# Total.net
KiCad netlist of a schematic drawn in Altium Designer
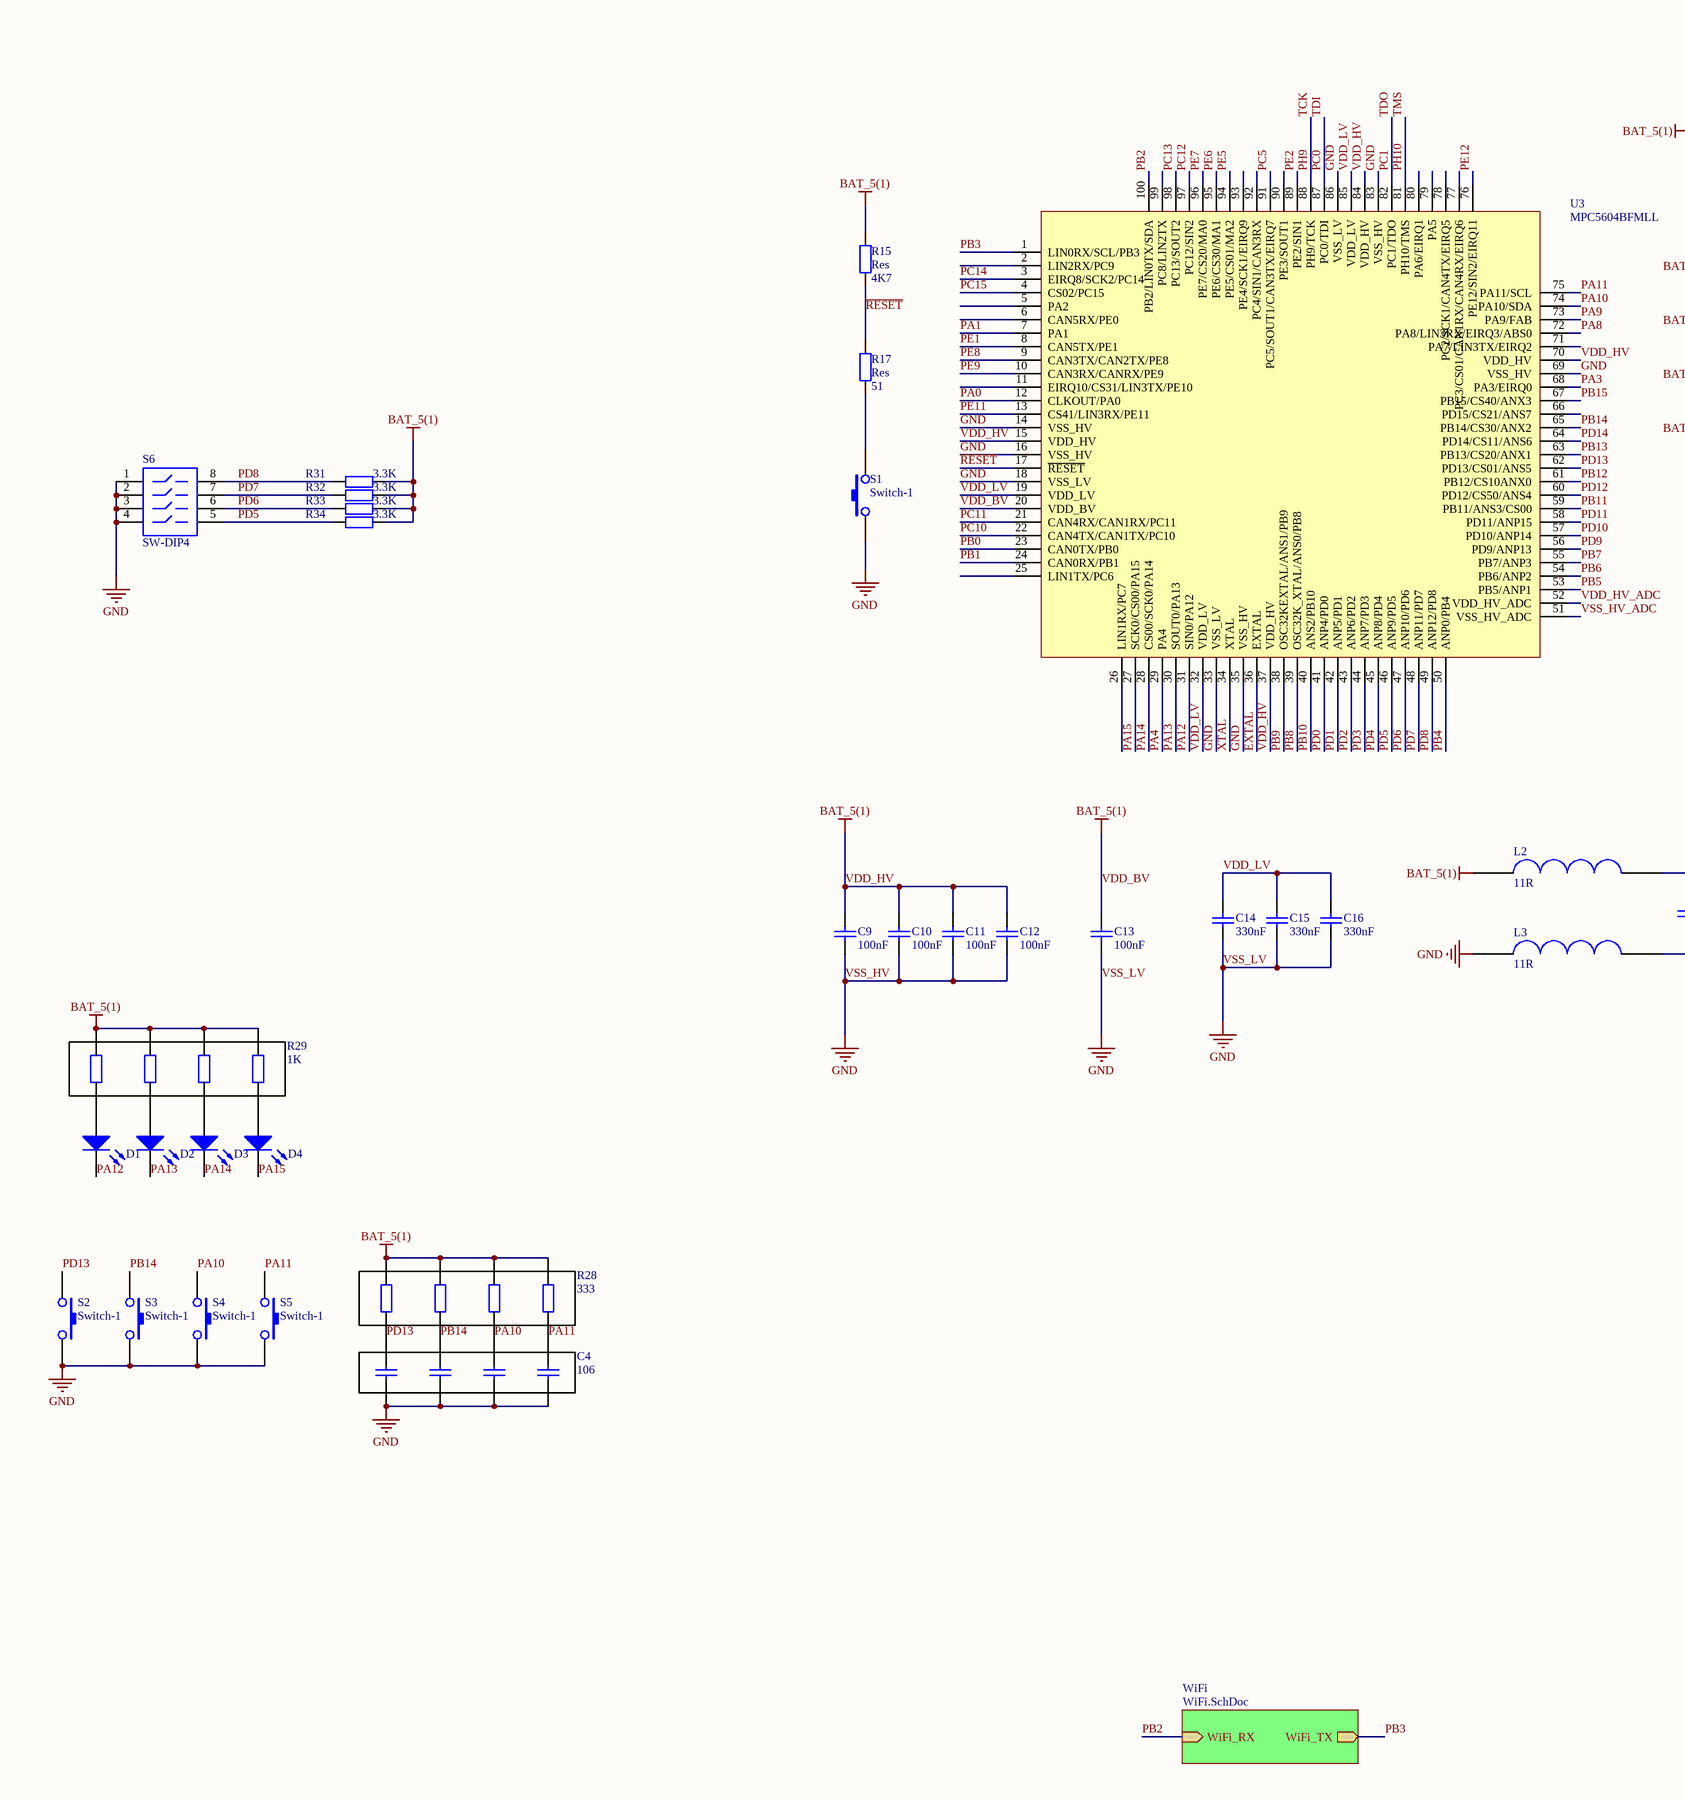
[diagram p0: Total.SchDoc, left]
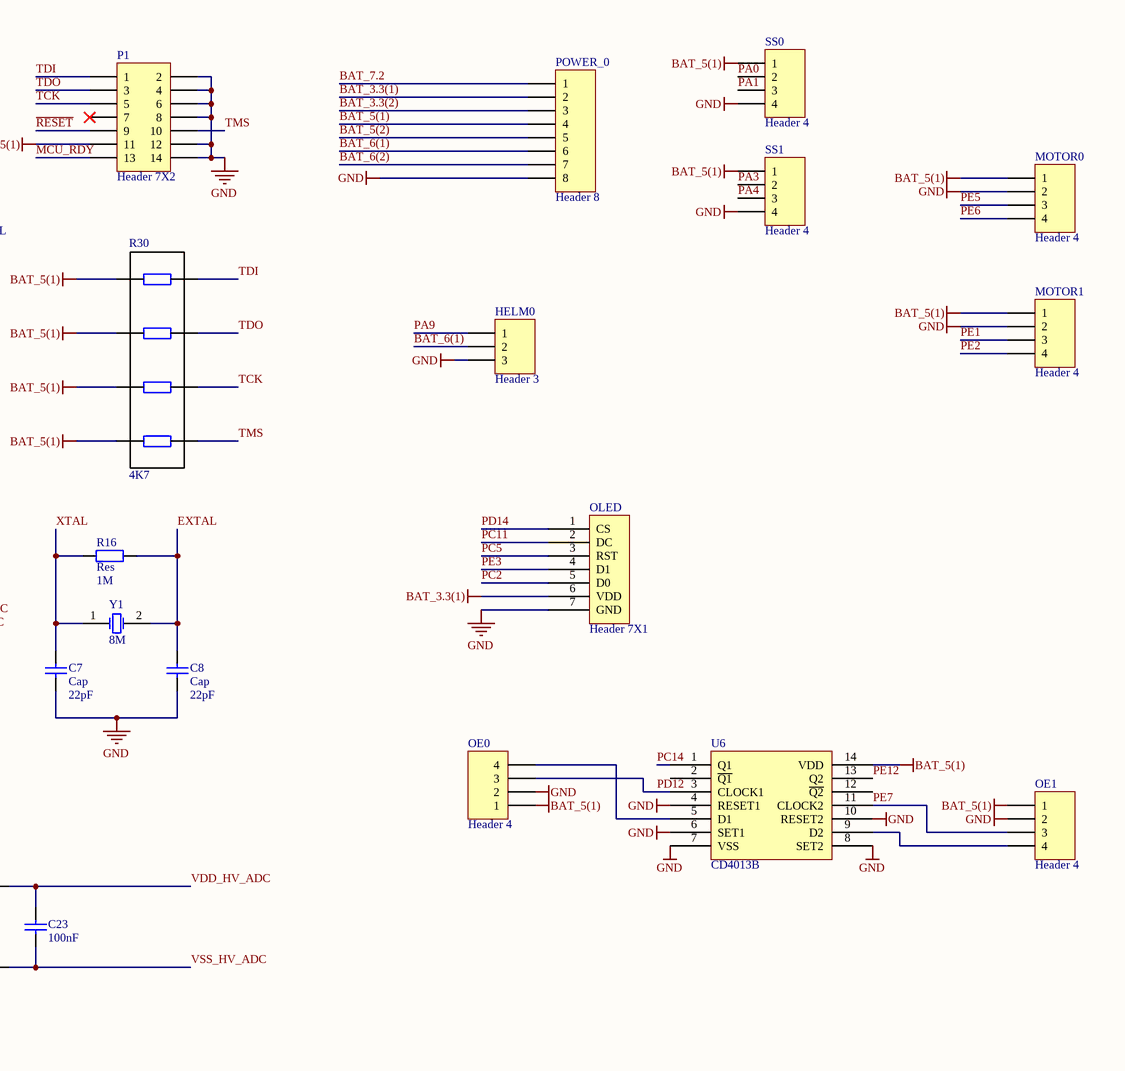
[diagram p1: Total.SchDoc, right]

(export (version "E")
  (design (tool "Eeschema 10.0.6"))
  (components
    (comp (ref "C4")
      (value "106")
      (footprint "8P4R-0603")
      (fields (field (name "Comment") "Cap x4"))
      (libsource (lib "SmartCarCreative") (part "Cap x4"))
    )
    (comp (ref "C7")
      (value "Cap")
      (footprint "0805 2")
      (description "Capacitor")
      (fields (field (name "ALTIUM_VALUE") "22pF") (field (name "PUBLISHER") "Altium Limited"))
      (libsource (lib "SmartCarCreative") (part "Cap"))
    )
    (comp (ref "C8")
      (value "Cap")
      (footprint "0805 2")
      (description "Capacitor")
      (fields (field (name "ALTIUM_VALUE") "22pF") (field (name "PUBLISHER") "Altium Limited"))
      (libsource (lib "SmartCarCreative") (part "Cap"))
    )
    (comp (ref "C9")
      (value "100nF")
      (footprint "0805 2")
      (description "Capacitor")
      (fields (field (name "Comment") "Cap") (field (name "PUBLISHER") "Altium Limited"))
      (libsource (lib "SmartCarCreative") (part "Cap"))
    )
    (comp (ref "C10")
      (value "100nF")
      (footprint "0805 2")
      (description "Capacitor")
      (fields (field (name "Comment") "Cap") (field (name "PUBLISHER") "Altium Limited"))
      (libsource (lib "SmartCarCreative") (part "Cap"))
    )
    (comp (ref "C11")
      (value "100nF")
      (footprint "0805 2")
      (description "Capacitor")
      (fields (field (name "Comment") "Cap") (field (name "PUBLISHER") "Altium Limited"))
      (libsource (lib "SmartCarCreative") (part "Cap"))
    )
    (comp (ref "C12")
      (value "100nF")
      (footprint "0805 2")
      (description "Capacitor")
      (fields (field (name "Comment") "Cap") (field (name "PUBLISHER") "Altium Limited"))
      (libsource (lib "SmartCarCreative") (part "Cap"))
    )
    (comp (ref "C13")
      (value "100nF")
      (footprint "0805 2")
      (description "Capacitor")
      (fields (field (name "Comment") "Cap") (field (name "PUBLISHER") "Altium Limited"))
      (libsource (lib "SmartCarCreative") (part "Cap"))
    )
    (comp (ref "C14")
      (value "330nF")
      (footprint "0805 2")
      (description "Capacitor")
      (fields (field (name "Comment") "Cap") (field (name "PUBLISHER") "Altium Limited"))
      (libsource (lib "SmartCarCreative") (part "Cap"))
    )
    (comp (ref "C15")
      (value "330nF")
      (footprint "0805 2")
      (description "Capacitor")
      (fields (field (name "Comment") "Cap") (field (name "PUBLISHER") "Altium Limited"))
      (libsource (lib "SmartCarCreative") (part "Cap"))
    )
    (comp (ref "C16")
      (value "330nF")
      (footprint "0805 2")
      (description "Capacitor")
      (fields (field (name "Comment") "Cap") (field (name "PUBLISHER") "Altium Limited"))
      (libsource (lib "SmartCarCreative") (part "Cap"))
    )
    (comp (ref "C23")
      (value "100nF")
      (footprint "0805 2")
      (description "Capacitor")
      (fields (field (name "Comment") "Cap") (field (name "PUBLISHER") "Altium Limited"))
      (libsource (lib "SmartCarCreative") (part "Cap"))
    )
    (comp (ref "D1") (value "LED") (footprint "0805 Pol 3") (libsource (lib "SmartCarCreative") (part "LED")))
    (comp (ref "D2") (value "LED") (footprint "0805 Pol 3") (libsource (lib "SmartCarCreative") (part "LED")))
    (comp (ref "D3") (value "LED") (footprint "0805 Pol 3") (libsource (lib "SmartCarCreative") (part "LED")))
    (comp (ref "D4") (value "LED") (footprint "0805 Pol 3") (libsource (lib "SmartCarCreative") (part "LED")))
    (comp (ref "HELM0")
      (value "Header 3")
      (footprint "HDR1X3")
      (description "Header, 3-Pin")
      (fields (field (name "PUBLISHER") "Altium Limited"))
      (libsource (lib "Miscellaneous Connectors") (part "Header 3"))
    )
    (comp (ref "L2")
      (value "11R")
      (footprint "0805 2")
      (fields (field (name "Comment") "Bead"))
      (libsource (lib "SmartCarCreative") (part "Bead"))
    )
    (comp (ref "L3")
      (value "11R")
      (footprint "0805 2")
      (fields (field (name "Comment") "Bead"))
      (libsource (lib "SmartCarCreative") (part "Bead"))
    )
    (comp (ref "MOTOR0")
      (value "Header 4")
      (footprint "HDR1X4")
      (description "Header, 4-Pin")
      (fields (field (name "PUBLISHER") "Altium Limited"))
      (libsource (lib "Miscellaneous Connectors") (part "Header 4"))
    )
    (comp (ref "MOTOR1")
      (value "Header 4")
      (footprint "HDR1X4")
      (description "Header, 4-Pin")
      (fields (field (name "PUBLISHER") "Altium Limited"))
      (libsource (lib "Miscellaneous Connectors") (part "Header 4"))
    )
    (comp (ref "OE0")
      (value "Header 4")
      (footprint "HDR1X4")
      (description "Header, 4-Pin")
      (fields (field (name "PUBLISHER") "Altium Limited"))
      (libsource (lib "") (part "Header 4_1"))
    )
    (comp (ref "OE1")
      (value "Header 4")
      (footprint "HDR1X4")
      (description "Header, 4-Pin")
      (fields (field (name "PUBLISHER") "Altium Limited"))
      (libsource (lib "Miscellaneous Connectors") (part "Header 4"))
    )
    (comp (ref "OLED")
      (value "Header 7X1")
      (footprint "OLED-chiusir")
      (libsource (lib "SmartCarCreative") (part "OLED-chiusir"))
    )
    (comp (ref "P1")
      (value "Header 7X2")
      (footprint "Header 2X7")
      (description "Header, 7-Pin, Dual row")
      (fields (field (name "PUBLISHER") "Altium Limited"))
      (libsource (lib "SmartCarCreative") (part "Header 7X2"))
    )
    (comp (ref "POWER_0")
      (value "Header 8")
      (footprint "XH2.54_8")
      (description "Header, 8-Pin")
      (fields (field (name "PUBLISHER") "Altium Limited"))
      (libsource (lib "SmartCarCreative") (part "Header 8"))
    )
    (comp (ref "R15")
      (value "Res")
      (footprint "0805 2")
      (description "Resistor")
      (fields (field (name "ALTIUM_VALUE") "4K7") (field (name "PUBLISHER") "Altium Limited"))
      (libsource (lib "") (part "Res_1"))
    )
    (comp (ref "R16")
      (value "Res")
      (footprint "0805 2")
      (description "Resistor")
      (fields (field (name "ALTIUM_VALUE") "1M") (field (name "PUBLISHER") "Altium Limited"))
      (libsource (lib "SmartCarCreative") (part "Res"))
    )
    (comp (ref "R17")
      (value "Res")
      (footprint "0805 2")
      (description "Resistor")
      (fields (field (name "ALTIUM_VALUE") "51") (field (name "PUBLISHER") "Altium Limited"))
      (libsource (lib "") (part "Res_1"))
    )
    (comp (ref "R28")
      (value "333")
      (footprint "8P4R-0603")
      (fields (field (name "Comment") "R x4"))
      (libsource (lib "") (part "Res x4_1"))
    )
    (comp (ref "R29")
      (value "1K")
      (footprint "8P4R-0603")
      (fields (field (name "Comment") "R x4"))
      (libsource (lib "") (part "Res x4_1"))
    )
    (comp (ref "R30")
      (value "4K7")
      (footprint "8P4R-0603")
      (fields (field (name "Comment") "R x4"))
      (libsource (lib "SmartCarCreative") (part "Res x4"))
    )
    (comp (ref "R31")
      (value "3.3K")
      (footprint "0805 2")
      (description "Resistor")
      (fields (field (name "Comment") "Res2") (field (name "PUBLISHER") "Altium Limited"))
      (libsource (lib "Miscellaneous Devices") (part "Res2"))
    )
    (comp (ref "R32")
      (value "3.3K")
      (footprint "0805 2")
      (description "Resistor")
      (fields (field (name "Comment") "Res2") (field (name "PUBLISHER") "Altium Limited"))
      (libsource (lib "Miscellaneous Devices") (part "Res2"))
    )
    (comp (ref "R33")
      (value "3.3K")
      (footprint "0805 2")
      (description "Resistor")
      (fields (field (name "Comment") "Res2") (field (name "PUBLISHER") "Altium Limited"))
      (libsource (lib "Miscellaneous Devices") (part "Res2"))
    )
    (comp (ref "R34")
      (value "3.3K")
      (footprint "0805 2")
      (description "Resistor")
      (fields (field (name "Comment") "Res2") (field (name "PUBLISHER") "Altium Limited"))
      (libsource (lib "Miscellaneous Devices") (part "Res2"))
    )
    (comp (ref "S1")
      (value "Switch-1")
      (footprint "轻触按键")
      (libsource (lib "SmartCarCreative") (part "Switch-1"))
    )
    (comp (ref "S2")
      (value "Switch-1")
      (footprint "轻触按键")
      (libsource (lib "SmartCarCreative") (part "Switch-1"))
    )
    (comp (ref "S3")
      (value "Switch-1")
      (footprint "轻触按键")
      (libsource (lib "SmartCarCreative") (part "Switch-1"))
    )
    (comp (ref "S4")
      (value "Switch-1")
      (footprint "轻触按键")
      (libsource (lib "SmartCarCreative") (part "Switch-1"))
    )
    (comp (ref "S5")
      (value "Switch-1")
      (footprint "轻触按键")
      (libsource (lib "SmartCarCreative") (part "Switch-1"))
    )
    (comp (ref "S6")
      (value "SW-DIP4")
      (footprint "Switch_4")
      (libsource (lib "SystemBoard2015") (part "SWITCH-4"))
    )
    (comp (ref "SS0")
      (value "Header 4")
      (footprint "HDR1X4")
      (description "Header, 4-Pin")
      (fields (field (name "PUBLISHER") "Altium Limited"))
      (libsource (lib "Miscellaneous Connectors") (part "Header 4"))
    )
    (comp (ref "SS1")
      (value "Header 4")
      (footprint "HDR1X4")
      (description "Header, 4-Pin")
      (fields (field (name "PUBLISHER") "Altium Limited"))
      (libsource (lib "Miscellaneous Connectors") (part "Header 4"))
    )
    (comp (ref "U3")
      (value "MPC5604BFMLL")
      (footprint "LQ_LQFP100")
      (libsource (lib "SmartCarCreative") (part "MPC5604BFMLL"))
    )
    (comp (ref "U6")
      (value "CD4013B")
      (footprint "TSOP-14")
      (description "CMOS Dual 'D'-Type Flip-Flop")
      (libsource (lib "SmartCarCreative") (part "CD4013B"))
    )
    (comp (ref "Y1")
      (value "8M")
      (footprint "5032 2")
      (description "Crystal Oscillator")
      (fields (field (name "Comment") "XTAL") (field (name "PUBLISHER") "Altium Limited"))
      (libsource (lib "SmartCarCreative") (part "XTAL"))
    )
  )
  (nets
    (net (code "1") (name "/BAT_3.3(2)") (class "Default")
      (node (ref "POWER_0") (pin "3") (pinfunction "3_3") (pintype "passive"))
    )
    (net (code "2") (name "/BAT_5(2)") (class "Default")
      (node (ref "POWER_0") (pin "5") (pinfunction "5_5") (pintype "passive"))
    )
    (net (code "3") (name "/BAT_6(1)") (class "Default")
      (node (ref "HELM0") (pin "2") (pinfunction "2_2") (pintype "passive"))
      (node (ref "POWER_0") (pin "6") (pinfunction "6_6") (pintype "passive"))
    )
    (net (code "4") (name "/BAT_6(2)") (class "Default")
      (node (ref "POWER_0") (pin "7") (pinfunction "7_7") (pintype "passive"))
    )
    (net (code "5") (name "/BAT_7.2") (class "Default")
      (node (ref "POWER_0") (pin "1") (pinfunction "1_1") (pintype "passive"))
    )
    (net (code "6") (name "/EXTAL") (class "Default")
      (node (ref "C8") (pin "2") (pinfunction "2_2") (pintype "passive"))
      (node (ref "R16") (pin "1") (pinfunction "1_1") (pintype "passive"))
      (node (ref "U3") (pin "36") (pinfunction "EXTAL_36") (pintype "passive"))
      (node (ref "Y1") (pin "2") (pinfunction "OSC2_2") (pintype "passive"))
    )
    (net (code "7") (name "/MCU_RDY") (class "Default")
      (node (ref "P1") (pin "13") (pinfunction "13_13") (pintype "passive"))
    )
    (net (code "8") (name "/PA0") (class "Default")
      (node (ref "SS0") (pin "2") (pinfunction "2_2") (pintype "passive"))
      (node (ref "U3") (pin "12") (pinfunction "CLKOUT/PA0_12") (pintype "passive"))
    )
    (net (code "9") (name "/PA1") (class "Default")
      (node (ref "SS0") (pin "3") (pinfunction "3_3") (pintype "passive"))
      (node (ref "U3") (pin "7") (pinfunction "PA1_7") (pintype "passive"))
    )
    (net (code "10") (name "/PA3") (class "Default")
      (node (ref "SS1") (pin "2") (pinfunction "2_2") (pintype "passive"))
      (node (ref "U3") (pin "68") (pinfunction "PA3/EIRQ0_68") (pintype "passive"))
    )
    (net (code "11") (name "/PA4") (class "Default")
      (node (ref "SS1") (pin "3") (pinfunction "3_3") (pintype "passive"))
      (node (ref "U3") (pin "29") (pinfunction "PA4_29") (pintype "passive"))
    )
    (net (code "12") (name "/PA8") (class "Default")
      (node (ref "U3") (pin "72") (pinfunction "PA8/LIN3RX/EIRQ3/ABS0_72") (pintype "passive"))
    )
    (net (code "13") (name "/PA9") (class "Default")
      (node (ref "HELM0") (pin "1") (pinfunction "1_1") (pintype "passive"))
      (node (ref "U3") (pin "73") (pinfunction "PA9/FAB_73") (pintype "passive"))
    )
    (net (code "14") (name "/PA10") (class "Default")
      (node (ref "C4") (pin "5") (pinfunction "5_5") (pintype "passive"))
      (node (ref "R28") (pin "6") (pinfunction "6_6") (pintype "passive"))
      (node (ref "S4") (pin "1") (pinfunction "1_1") (pintype "passive"))
      (node (ref "U3") (pin "74") (pinfunction "PA10/SDA_74") (pintype "passive"))
    )
    (net (code "15") (name "/PA11") (class "Default")
      (node (ref "C4") (pin "7") (pinfunction "7_7") (pintype "passive"))
      (node (ref "R28") (pin "8") (pinfunction "8_8") (pintype "passive"))
      (node (ref "S5") (pin "1") (pinfunction "1_1") (pintype "passive"))
      (node (ref "U3") (pin "75") (pinfunction "PA11/SCL_75") (pintype "passive"))
    )
    (net (code "16") (name "/PA12") (class "Default")
      (node (ref "D1") (pin "2") (pinfunction "K_2") (pintype "passive"))
      (node (ref "U3") (pin "31") (pinfunction "SIN0/PA12_31") (pintype "passive"))
    )
    (net (code "17") (name "/PA13") (class "Default")
      (node (ref "D2") (pin "2") (pinfunction "K_2") (pintype "passive"))
      (node (ref "U3") (pin "30") (pinfunction "SOUT0/PA13_30") (pintype "passive"))
    )
    (net (code "18") (name "/PA14") (class "Default")
      (node (ref "D3") (pin "2") (pinfunction "K_2") (pintype "passive"))
      (node (ref "U3") (pin "28") (pinfunction "CS00/SCK0/PA14_28") (pintype "passive"))
    )
    (net (code "19") (name "/PA15") (class "Default")
      (node (ref "D4") (pin "2") (pinfunction "K_2") (pintype "passive"))
      (node (ref "U3") (pin "27") (pinfunction "SCK0/CS00/PA15_27") (pintype "passive"))
    )
    (net (code "20") (name "/PB0") (class "Default")
      (node (ref "U3") (pin "23") (pinfunction "CAN0TX/PB0_23") (pintype "passive"))
    )
    (net (code "21") (name "/PB1") (class "Default")
      (node (ref "U3") (pin "24") (pinfunction "CAN0RX/PB1_24") (pintype "passive"))
    )
    (net (code "22") (name "/PB2") (class "Default")
      (node (ref "U3") (pin "100") (pinfunction "PB2/LIN0TX/SDA_100") (pintype "passive"))
    )
    (net (code "23") (name "/PB3") (class "Default")
      (node (ref "U3") (pin "1") (pinfunction "LIN0RX/SCL/PB3_1") (pintype "passive"))
    )
    (net (code "24") (name "/PB4") (class "Default")
      (node (ref "U3") (pin "50") (pinfunction "ANP0/PB4_50") (pintype "passive"))
    )
    (net (code "25") (name "/PB5") (class "Default")
      (node (ref "U3") (pin "53") (pinfunction "PB5/ANP1_53") (pintype "passive"))
    )
    (net (code "26") (name "/PB6") (class "Default")
      (node (ref "U3") (pin "54") (pinfunction "PB6/ANP2_54") (pintype "passive"))
    )
    (net (code "27") (name "/PB7") (class "Default")
      (node (ref "U3") (pin "55") (pinfunction "PB7/ANP3_55") (pintype "passive"))
    )
    (net (code "28") (name "/PB8") (class "Default")
      (node (ref "U3") (pin "39") (pinfunction "OSC32K_XTAL/ANS0/PB8_39") (pintype "passive"))
    )
    (net (code "29") (name "/PB9") (class "Default")
      (node (ref "U3") (pin "38") (pinfunction "OSC32KEXTAL/ANS1/PB9_38") (pintype "passive"))
    )
    (net (code "30") (name "/PB10") (class "Default")
      (node (ref "U3") (pin "40") (pinfunction "ANS2/PB10_40") (pintype "passive"))
    )
    (net (code "31") (name "/PB11") (class "Default")
      (node (ref "U3") (pin "59") (pinfunction "PB11/ANS3/CS00_59") (pintype "passive"))
    )
    (net (code "32") (name "/PB12") (class "Default")
      (node (ref "U3") (pin "61") (pinfunction "PB12/CS10ANX0_61") (pintype "passive"))
    )
    (net (code "33") (name "/PB13") (class "Default")
      (node (ref "U3") (pin "63") (pinfunction "PB13/CS20/ANX1_63") (pintype "passive"))
    )
    (net (code "34") (name "/PB14") (class "Default")
      (node (ref "C4") (pin "3") (pinfunction "3_3") (pintype "passive"))
      (node (ref "R28") (pin "4") (pinfunction "4_4") (pintype "passive"))
      (node (ref "S3") (pin "1") (pinfunction "1_1") (pintype "passive"))
      (node (ref "U3") (pin "65") (pinfunction "PB14/CS30/ANX2_65") (pintype "passive"))
    )
    (net (code "35") (name "/PB15") (class "Default")
      (node (ref "U3") (pin "67") (pinfunction "PB15/CS40/ANX3_67") (pintype "passive"))
    )
    (net (code "36") (name "/PC0") (class "Default")
      (node (ref "P1") (pin "1") (pinfunction "1_1") (pintype "passive"))
      (node (ref "R30") (pin "1") (pinfunction "1_1") (pintype "passive"))
      (node (ref "U3") (pin "87") (pinfunction "PC0/TDI_87") (pintype "passive"))
    )
    (net (code "37") (name "/PC1") (class "Default")
      (node (ref "P1") (pin "3") (pinfunction "3_3") (pintype "passive"))
      (node (ref "R30") (pin "3") (pinfunction "3_3") (pintype "passive"))
      (node (ref "U3") (pin "82") (pinfunction "PC1/TDO_82") (pintype "passive"))
    )
    (net (code "38") (name "/PC2") (class "Default")
      (node (ref "OLED") (pin "5") (pinfunction "D0_5") (pintype "passive"))
    )
    (net (code "39") (name "/PC5") (class "Default")
      (node (ref "OLED") (pin "3") (pinfunction "RST_3") (pintype "passive"))
      (node (ref "U3") (pin "91") (pinfunction "PC5/SOUT1/CAN3TX/EIRQ7_91") (pintype "passive"))
    )
    (net (code "40") (name "/PC10") (class "Default")
      (node (ref "U3") (pin "22") (pinfunction "CAN4TX/CAN1TX/PC10_22") (pintype "passive"))
    )
    (net (code "41") (name "/PC11") (class "Default")
      (node (ref "OLED") (pin "2") (pinfunction "DC_2") (pintype "passive"))
      (node (ref "U3") (pin "21") (pinfunction "CAN4RX/CAN1RX/PC11_21") (pintype "passive"))
    )
    (net (code "42") (name "/PC12") (class "Default")
      (node (ref "U3") (pin "97") (pinfunction "PC12/SIN2_97") (pintype "passive"))
    )
    (net (code "43") (name "/PC13") (class "Default")
      (node (ref "U3") (pin "98") (pinfunction "PC13/SOUT2_98") (pintype "passive"))
    )
    (net (code "44") (name "/PC14") (class "Default")
      (node (ref "U3") (pin "3") (pinfunction "EIRQ8/SCK2/PC14_3") (pintype "passive"))
      (node (ref "U6") (pin "1") (pinfunction "Q1_1") (pintype "passive"))
    )
    (net (code "45") (name "/PC15") (class "Default")
      (node (ref "U3") (pin "4") (pinfunction "CS02/PC15_4") (pintype "passive"))
    )
    (net (code "46") (name "/PD0") (class "Default")
      (node (ref "U3") (pin "41") (pinfunction "ANP4/PD0_41") (pintype "passive"))
    )
    (net (code "47") (name "/PD1") (class "Default")
      (node (ref "U3") (pin "42") (pinfunction "ANP5/PD1_42") (pintype "passive"))
    )
    (net (code "48") (name "/PD2") (class "Default")
      (node (ref "U3") (pin "43") (pinfunction "ANP6/PD2_43") (pintype "passive"))
    )
    (net (code "49") (name "/PD3") (class "Default")
      (node (ref "U3") (pin "44") (pinfunction "ANP7/PD3_44") (pintype "passive"))
    )
    (net (code "50") (name "/PD4") (class "Default")
      (node (ref "U3") (pin "45") (pinfunction "ANP8/PD4_45") (pintype "passive"))
    )
    (net (code "51") (name "/PD5") (class "Default")
      (node (ref "R34") (pin "2") (pinfunction "2_2") (pintype "passive"))
      (node (ref "S6") (pin "5") (pinfunction "5_5") (pintype "passive"))
      (node (ref "U3") (pin "46") (pinfunction "ANP9/PD5_46") (pintype "passive"))
    )
    (net (code "52") (name "/PD6") (class "Default")
      (node (ref "R33") (pin "2") (pinfunction "2_2") (pintype "passive"))
      (node (ref "S6") (pin "6") (pinfunction "6_6") (pintype "passive"))
      (node (ref "U3") (pin "47") (pinfunction "ANP10/PD6_47") (pintype "passive"))
    )
    (net (code "53") (name "/PD7") (class "Default")
      (node (ref "R32") (pin "2") (pinfunction "2_2") (pintype "passive"))
      (node (ref "S6") (pin "7") (pinfunction "7_7") (pintype "passive"))
      (node (ref "U3") (pin "48") (pinfunction "ANP11/PD7_48") (pintype "passive"))
    )
    (net (code "54") (name "/PD8") (class "Default")
      (node (ref "R31") (pin "2") (pinfunction "2_2") (pintype "passive"))
      (node (ref "S6") (pin "8") (pinfunction "8_8") (pintype "passive"))
      (node (ref "U3") (pin "49") (pinfunction "ANP12/PD8_49") (pintype "passive"))
    )
    (net (code "55") (name "/PD9") (class "Default")
      (node (ref "U3") (pin "56") (pinfunction "PD9/ANP13_56") (pintype "passive"))
    )
    (net (code "56") (name "/PD10") (class "Default")
      (node (ref "U3") (pin "57") (pinfunction "PD10/ANP14_57") (pintype "passive"))
    )
    (net (code "57") (name "/PD11") (class "Default")
      (node (ref "U3") (pin "58") (pinfunction "PD11/ANP15_58") (pintype "passive"))
    )
    (net (code "58") (name "/PD12") (class "Default")
      (node (ref "OE0") (pin "3") (pinfunction "3_3") (pintype "passive"))
      (node (ref "U3") (pin "60") (pinfunction "PD12/CS50/ANS4_60") (pintype "passive"))
      (node (ref "U6") (pin "3") (pinfunction "CLOCK1_3") (pintype "passive"))
    )
    (net (code "59") (name "/PD13") (class "Default")
      (node (ref "C4") (pin "1") (pinfunction "1_1") (pintype "passive"))
      (node (ref "R28") (pin "2") (pinfunction "2_2") (pintype "passive"))
      (node (ref "S2") (pin "1") (pinfunction "1_1") (pintype "passive"))
      (node (ref "U3") (pin "62") (pinfunction "PD13/CS01/ANS5_62") (pintype "passive"))
    )
    (net (code "60") (name "/PD14") (class "Default")
      (node (ref "OLED") (pin "1") (pinfunction "CS_1") (pintype "passive"))
      (node (ref "U3") (pin "64") (pinfunction "PD14/CS11/ANS6_64") (pintype "passive"))
    )
    (net (code "61") (name "/PE1") (class "Default")
      (node (ref "MOTOR1") (pin "3") (pinfunction "3_3") (pintype "passive"))
      (node (ref "U3") (pin "8") (pinfunction "CAN5TX/PE1_8") (pintype "passive"))
    )
    (net (code "62") (name "/PE2") (class "Default")
      (node (ref "MOTOR1") (pin "4") (pinfunction "4_4") (pintype "passive"))
      (node (ref "U3") (pin "89") (pinfunction "PE2/SIN1_89") (pintype "passive"))
    )
    (net (code "63") (name "/PE3") (class "Default")
      (node (ref "OLED") (pin "4") (pinfunction "D1_4") (pintype "passive"))
    )
    (net (code "64") (name "/PE5") (class "Default")
      (node (ref "MOTOR0") (pin "3") (pinfunction "3_3") (pintype "passive"))
      (node (ref "U3") (pin "94") (pinfunction "PE5/CS01/MA2_94") (pintype "passive"))
    )
    (net (code "65") (name "/PE6") (class "Default")
      (node (ref "MOTOR0") (pin "4") (pinfunction "4_4") (pintype "passive"))
      (node (ref "U3") (pin "95") (pinfunction "PE6/CS30/MA1_95") (pintype "passive"))
    )
    (net (code "66") (name "/PE7") (class "Default")
      (node (ref "OE1") (pin "3") (pinfunction "3_3") (pintype "passive"))
      (node (ref "U3") (pin "96") (pinfunction "PE7/CS20/MA0_96") (pintype "passive"))
      (node (ref "U6") (pin "11") (pinfunction "CLOCK2_11") (pintype "passive"))
    )
    (net (code "67") (name "/PE8") (class "Default")
      (node (ref "U3") (pin "9") (pinfunction "CAN3TX/CAN2TX/PE8_9") (pintype "passive"))
    )
    (net (code "68") (name "/PE9") (class "Default")
      (node (ref "U3") (pin "10") (pinfunction "CAN3RX/CANRX/PE9_10") (pintype "passive"))
    )
    (net (code "69") (name "/PE11") (class "Default")
      (node (ref "U3") (pin "13") (pinfunction "CS41/LIN3RX/PE11_13") (pintype "passive"))
    )
    (net (code "70") (name "/PE12") (class "Default")
      (node (ref "U3") (pin "76") (pinfunction "PE12/SIN2/EIRQ11_76") (pintype "passive"))
      (node (ref "U6") (pin "13") (pinfunction "Q2_13") (pintype "passive"))
    )
    (net (code "71") (name "/PH9") (class "Default")
      (node (ref "P1") (pin "5") (pinfunction "5_5") (pintype "passive"))
      (node (ref "R30") (pin "5") (pinfunction "5_5") (pintype "passive"))
      (node (ref "U3") (pin "88") (pinfunction "PH9/TCK_88") (pintype "passive"))
    )
    (net (code "72") (name "/PH10") (class "Default")
      (node (ref "P1") (pin "10") (pinfunction "10_10") (pintype "passive"))
      (node (ref "R30") (pin "7") (pinfunction "7_7") (pintype "passive"))
      (node (ref "U3") (pin "81") (pinfunction "PH10/TMS_81") (pintype "passive"))
    )
    (net (code "73") (name "/VDD_HV_ADC") (class "Default")
      (node (ref "C23") (pin "2") (pinfunction "2_2") (pintype "passive"))
      (node (ref "L2") (pin "2") (pinfunction "2_2") (pintype "passive"))
      (node (ref "U3") (pin "52") (pinfunction "VDD_HV_ADC_52") (pintype "passive"))
    )
    (net (code "74") (name "/VDD_LV") (class "Default")
      (node (ref "C14") (pin "2") (pinfunction "2_2") (pintype "passive"))
      (node (ref "C15") (pin "2") (pinfunction "2_2") (pintype "passive"))
      (node (ref "C16") (pin "2") (pinfunction "2_2") (pintype "passive"))
      (node (ref "U3") (pin "19") (pinfunction "VDD_LV_19") (pintype "passive"))
      (node (ref "U3") (pin "32") (pinfunction "VDD_LV_32") (pintype "passive"))
      (node (ref "U3") (pin "85") (pinfunction "VDD_LV_85") (pintype "passive"))
    )
    (net (code "75") (name "/VSS_HV_ADC") (class "Default")
      (node (ref "C23") (pin "1") (pinfunction "1_1") (pintype "passive"))
      (node (ref "L3") (pin "2") (pinfunction "2_2") (pintype "passive"))
      (node (ref "U3") (pin "51") (pinfunction "VSS_HV_ADC_51") (pintype "passive"))
    )
    (net (code "76") (name "/XTAL") (class "Default")
      (node (ref "C7") (pin "2") (pinfunction "2_2") (pintype "passive"))
      (node (ref "R16") (pin "2") (pinfunction "2_2") (pintype "passive"))
      (node (ref "U3") (pin "34") (pinfunction "XTAL_34") (pintype "passive"))
      (node (ref "Y1") (pin "1") (pinfunction "OSC1_1") (pintype "passive"))
    )
    (net (code "77") (name "/~{RESET}") (class "Default")
      (node (ref "P1") (pin "9") (pinfunction "9_9") (pintype "passive"))
      (node (ref "R15") (pin "1") (pinfunction "1_1") (pintype "passive"))
      (node (ref "R17") (pin "2") (pinfunction "2_2") (pintype "passive"))
      (node (ref "U3") (pin "17") (pinfunction "~{RESET}_17") (pintype "passive"))
    )
    (net (code "78") (name "BAT_3.3(1)") (class "Default")
      (node (ref "OLED") (pin "6") (pinfunction "VDD_6") (pintype "passive"))
      (node (ref "POWER_0") (pin "2") (pinfunction "2_2") (pintype "passive"))
    )
    (net (code "79") (name "BAT_5(1)") (class "Default")
      (node (ref "C10") (pin "2") (pinfunction "2_2") (pintype "passive"))
      (node (ref "C11") (pin "2") (pinfunction "2_2") (pintype "passive"))
      (node (ref "C12") (pin "2") (pinfunction "2_2") (pintype "passive"))
      (node (ref "C13") (pin "2") (pinfunction "2_2") (pintype "passive"))
      (node (ref "C9") (pin "2") (pinfunction "2_2") (pintype "passive"))
      (node (ref "L2") (pin "1") (pinfunction "1_1") (pintype "passive"))
      (node (ref "MOTOR0") (pin "1") (pinfunction "1_1") (pintype "passive"))
      (node (ref "MOTOR1") (pin "1") (pinfunction "1_1") (pintype "passive"))
      (node (ref "OE0") (pin "1") (pinfunction "1_1") (pintype "passive"))
      (node (ref "OE1") (pin "1") (pinfunction "1_1") (pintype "passive"))
      (node (ref "P1") (pin "11") (pinfunction "11_11") (pintype "passive"))
      (node (ref "POWER_0") (pin "4") (pinfunction "4_4") (pintype "passive"))
      (node (ref "R15") (pin "2") (pinfunction "2_2") (pintype "passive"))
      (node (ref "R28") (pin "1") (pinfunction "1_1") (pintype "passive"))
      (node (ref "R28") (pin "3") (pinfunction "3_3") (pintype "passive"))
      (node (ref "R28") (pin "5") (pinfunction "5_5") (pintype "passive"))
      (node (ref "R28") (pin "7") (pinfunction "7_7") (pintype "passive"))
      (node (ref "R29") (pin "1") (pinfunction "1_1") (pintype "passive"))
      (node (ref "R29") (pin "3") (pinfunction "3_3") (pintype "passive"))
      (node (ref "R29") (pin "5") (pinfunction "5_5") (pintype "passive"))
      (node (ref "R29") (pin "7") (pinfunction "7_7") (pintype "passive"))
      (node (ref "R30") (pin "2") (pinfunction "2_2") (pintype "passive"))
      (node (ref "R30") (pin "4") (pinfunction "4_4") (pintype "passive"))
      (node (ref "R30") (pin "6") (pinfunction "6_6") (pintype "passive"))
      (node (ref "R30") (pin "8") (pinfunction "8_8") (pintype "passive"))
      (node (ref "R31") (pin "1") (pinfunction "1_1") (pintype "passive"))
      (node (ref "R32") (pin "1") (pinfunction "1_1") (pintype "passive"))
      (node (ref "R33") (pin "1") (pinfunction "1_1") (pintype "passive"))
      (node (ref "R34") (pin "1") (pinfunction "1_1") (pintype "passive"))
      (node (ref "SS0") (pin "1") (pinfunction "1_1") (pintype "passive"))
      (node (ref "SS1") (pin "1") (pinfunction "1_1") (pintype "passive"))
      (node (ref "U3") (pin "15") (pinfunction "VDD_HV_15") (pintype "passive"))
      (node (ref "U3") (pin "20") (pinfunction "VDD_BV_20") (pintype "passive"))
      (node (ref "U3") (pin "37") (pinfunction "VDD_HV_37") (pintype "passive"))
      (node (ref "U3") (pin "70") (pinfunction "VDD_HV_70") (pintype "passive"))
      (node (ref "U3") (pin "84") (pinfunction "VDD_HV_84") (pintype "passive"))
      (node (ref "U6") (pin "14") (pinfunction "VDD_14") (pintype "passive"))
    )
    (net (code "80") (name "GND") (class "Default")
      (node (ref "C10") (pin "1") (pinfunction "1_1") (pintype "passive"))
      (node (ref "C11") (pin "1") (pinfunction "1_1") (pintype "passive"))
      (node (ref "C12") (pin "1") (pinfunction "1_1") (pintype "passive"))
      (node (ref "C13") (pin "1") (pinfunction "1_1") (pintype "passive"))
      (node (ref "C14") (pin "1") (pinfunction "1_1") (pintype "passive"))
      (node (ref "C15") (pin "1") (pinfunction "1_1") (pintype "passive"))
      (node (ref "C16") (pin "1") (pinfunction "1_1") (pintype "passive"))
      (node (ref "C4") (pin "2") (pinfunction "2_2") (pintype "passive"))
      (node (ref "C4") (pin "4") (pinfunction "4_4") (pintype "passive"))
      (node (ref "C4") (pin "6") (pinfunction "6_6") (pintype "passive"))
      (node (ref "C4") (pin "8") (pinfunction "8_8") (pintype "passive"))
      (node (ref "C7") (pin "1") (pinfunction "1_1") (pintype "passive"))
      (node (ref "C8") (pin "1") (pinfunction "1_1") (pintype "passive"))
      (node (ref "C9") (pin "1") (pinfunction "1_1") (pintype "passive"))
      (node (ref "HELM0") (pin "3") (pinfunction "3_3") (pintype "passive"))
      (node (ref "L3") (pin "1") (pinfunction "1_1") (pintype "passive"))
      (node (ref "MOTOR0") (pin "2") (pinfunction "2_2") (pintype "passive"))
      (node (ref "MOTOR1") (pin "2") (pinfunction "2_2") (pintype "passive"))
      (node (ref "OE0") (pin "2") (pinfunction "2_2") (pintype "passive"))
      (node (ref "OE1") (pin "2") (pinfunction "2_2") (pintype "passive"))
      (node (ref "OLED") (pin "7") (pinfunction "GND_7") (pintype "passive"))
      (node (ref "P1") (pin "12") (pinfunction "12_12") (pintype "passive"))
      (node (ref "P1") (pin "14") (pinfunction "14_14") (pintype "passive"))
      (node (ref "P1") (pin "2") (pinfunction "2_2") (pintype "passive"))
      (node (ref "P1") (pin "4") (pinfunction "4_4") (pintype "passive"))
      (node (ref "P1") (pin "6") (pinfunction "6_6") (pintype "passive"))
      (node (ref "P1") (pin "8") (pinfunction "8_8") (pintype "passive"))
      (node (ref "POWER_0") (pin "8") (pinfunction "8_8") (pintype "passive"))
      (node (ref "S1") (pin "1") (pinfunction "1_1") (pintype "passive"))
      (node (ref "S2") (pin "2") (pinfunction "2_2") (pintype "passive"))
      (node (ref "S3") (pin "2") (pinfunction "2_2") (pintype "passive"))
      (node (ref "S4") (pin "2") (pinfunction "2_2") (pintype "passive"))
      (node (ref "S5") (pin "2") (pinfunction "2_2") (pintype "passive"))
      (node (ref "S6") (pin "1") (pinfunction "1_1") (pintype "passive"))
      (node (ref "S6") (pin "2") (pinfunction "2_2") (pintype "passive"))
      (node (ref "S6") (pin "3") (pinfunction "3_3") (pintype "passive"))
      (node (ref "S6") (pin "4") (pinfunction "4_4") (pintype "passive"))
      (node (ref "SS0") (pin "4") (pinfunction "4_4") (pintype "passive"))
      (node (ref "SS1") (pin "4") (pinfunction "4_4") (pintype "passive"))
      (node (ref "U3") (pin "14") (pinfunction "VSS_HV_14") (pintype "passive"))
      (node (ref "U3") (pin "16") (pinfunction "VSS_HV_16") (pintype "passive"))
      (node (ref "U3") (pin "18") (pinfunction "VSS_LV_18") (pintype "passive"))
      (node (ref "U3") (pin "33") (pinfunction "VSS_LV_33") (pintype "passive"))
      (node (ref "U3") (pin "35") (pinfunction "VSS_HV_35") (pintype "passive"))
      (node (ref "U3") (pin "69") (pinfunction "VSS_HV_69") (pintype "passive"))
      (node (ref "U3") (pin "83") (pinfunction "VSS_HV_83") (pintype "passive"))
      (node (ref "U3") (pin "86") (pinfunction "VSS_LV_86") (pintype "passive"))
      (node (ref "U6") (pin "10") (pinfunction "RESET2_10") (pintype "passive"))
      (node (ref "U6") (pin "4") (pinfunction "RESET1_4") (pintype "passive"))
      (node (ref "U6") (pin "6") (pinfunction "SET1_6") (pintype "passive"))
      (node (ref "U6") (pin "7") (pinfunction "VSS_7") (pintype "passive"))
      (node (ref "U6") (pin "8") (pinfunction "SET2_8") (pintype "passive"))
    )
    (net (code "81") (name "Net-(D1-A)") (class "Default")
      (node (ref "D1") (pin "1") (pinfunction "A_1") (pintype "passive"))
      (node (ref "R29") (pin "2") (pinfunction "2_2") (pintype "passive"))
    )
    (net (code "82") (name "Net-(D2-A)") (class "Default")
      (node (ref "D2") (pin "1") (pinfunction "A_1") (pintype "passive"))
      (node (ref "R29") (pin "4") (pinfunction "4_4") (pintype "passive"))
    )
    (net (code "83") (name "Net-(D3-A)") (class "Default")
      (node (ref "D3") (pin "1") (pinfunction "A_1") (pintype "passive"))
      (node (ref "R29") (pin "6") (pinfunction "6_6") (pintype "passive"))
    )
    (net (code "84") (name "Net-(D4-A)") (class "Default")
      (node (ref "D4") (pin "1") (pinfunction "A_1") (pintype "passive"))
      (node (ref "R29") (pin "8") (pinfunction "8_8") (pintype "passive"))
    )
    (net (code "85") (name "Net-(R17-Pad1)") (class "Default")
      (node (ref "R17") (pin "1") (pinfunction "1_1") (pintype "passive"))
      (node (ref "S1") (pin "2") (pinfunction "2_2") (pintype "passive"))
    )
    (net (code "86") (name "Net-(U6-D1)") (class "Default")
      (node (ref "OE0") (pin "4") (pinfunction "4_4") (pintype "passive"))
      (node (ref "U6") (pin "5") (pinfunction "D1_5") (pintype "passive"))
    )
    (net (code "87") (name "Net-(U6-D2)") (class "Default")
      (node (ref "OE1") (pin "4") (pinfunction "4_4") (pintype "passive"))
      (node (ref "U6") (pin "9") (pinfunction "D2_9") (pintype "passive"))
    )
    (net (code "88") (name "unconnected-(P1-Pad7)") (class "Default")
      (node (ref "P1") (pin "7") (pinfunction "7_7") (pintype "passive+no_connect"))
    )
    (net (code "89") (name "unconnected-(U3-CAN5RX{slash}PE0-Pad6)") (class "Default")
      (node (ref "U3") (pin "6") (pinfunction "CAN5RX/PE0_6") (pintype "passive"))
    )
    (net (code "90") (name "unconnected-(U3-EIRQ10{slash}CS31{slash}LIN3TX{slash}PE10-Pad11)") (class "Default")
      (node (ref "U3") (pin "11") (pinfunction "EIRQ10/CS31/LIN3TX/PE10_11") (pintype "passive"))
    )
    (net (code "91") (name "unconnected-(U3-LIN1RX{slash}PC7-Pad26)") (class "Default")
      (node (ref "U3") (pin "26") (pinfunction "LIN1RX/PC7_26") (pintype "passive"))
    )
    (net (code "92") (name "unconnected-(U3-LIN1TX{slash}PC6-Pad25)") (class "Default")
      (node (ref "U3") (pin "25") (pinfunction "LIN1TX/PC6_25") (pintype "passive"))
    )
    (net (code "93") (name "unconnected-(U3-LIN2RX{slash}PC9-Pad2)") (class "Default")
      (node (ref "U3") (pin "2") (pinfunction "LIN2RX/PC9_2") (pintype "passive"))
    )
    (net (code "94") (name "unconnected-(U3-PA2-Pad5)") (class "Default")
      (node (ref "U3") (pin "5") (pinfunction "PA2_5") (pintype "passive"))
    )
    (net (code "95") (name "unconnected-(U3-PA5-Pad79)") (class "Default")
      (node (ref "U3") (pin "79") (pinfunction "PA5_79") (pintype "passive"))
    )
    (net (code "96") (name "unconnected-(U3-PA6{slash}EIRQ1-Pad80)") (class "Default")
      (node (ref "U3") (pin "80") (pinfunction "PA6/EIRQ1_80") (pintype "passive"))
    )
    (net (code "97") (name "unconnected-(U3-PA7{slash}LIN3TX{slash}EIRQ2-Pad71)") (class "Default")
      (node (ref "U3") (pin "71") (pinfunction "PA7/LIN3TX/EIRQ2_71") (pintype "passive"))
    )
    (net (code "98") (name "unconnected-(U3-PC2{slash}SCK1{slash}CAN4TX{slash}EIRQ5-Pad78)") (class "Default")
      (node (ref "U3") (pin "78") (pinfunction "PC2/SCK1/CAN4TX/EIRQ5_78") (pintype "passive"))
    )
    (net (code "99") (name "unconnected-(U3-PC3{slash}CS01{slash}CAN1RX{slash}CAN4RX{slash}EIRQ6-Pad77)") (class "Default")
      (node (ref "U3") (pin "77") (pinfunction "PC3/CS01/CAN1RX/CAN4RX/EIRQ6_77") (pintype "passive"))
    )
    (net (code "100") (name "unconnected-(U3-PC4{slash}SIN1{slash}CAN3RX-Pad92)") (class "Default")
      (node (ref "U3") (pin "92") (pinfunction "PC4/SIN1/CAN3RX_92") (pintype "passive"))
    )
    (net (code "101") (name "unconnected-(U3-PC8{slash}LIN2TX-Pad99)") (class "Default")
      (node (ref "U3") (pin "99") (pinfunction "PC8/LIN2TX_99") (pintype "passive"))
    )
    (net (code "102") (name "unconnected-(U3-PD15{slash}CS21{slash}ANS7-Pad66)") (class "Default")
      (node (ref "U3") (pin "66") (pinfunction "PD15/CS21/ANS7_66") (pintype "passive"))
    )
    (net (code "103") (name "unconnected-(U3-PE3{slash}SOUT1-Pad90)") (class "Default")
      (node (ref "U3") (pin "90") (pinfunction "PE3/SOUT1_90") (pintype "passive"))
    )
    (net (code "104") (name "unconnected-(U3-PE4{slash}SCK1{slash}EIRQ9-Pad93)") (class "Default")
      (node (ref "U3") (pin "93") (pinfunction "PE4/SCK1/EIRQ9_93") (pintype "passive"))
    )
    (net (code "105") (name "unconnected-(U6-~{Q1}-Pad2)") (class "Default")
      (node (ref "U6") (pin "2") (pinfunction "~{Q1}_2") (pintype "passive"))
    )
    (net (code "106") (name "unconnected-(U6-~{Q2}-Pad12)") (class "Default")
      (node (ref "U6") (pin "12") (pinfunction "~{Q2}_12") (pintype "passive"))
    )
  )
)
